# MCU021_V1_0_Target_Device.net
KiCad netlist of a schematic drawn in Altium Designer
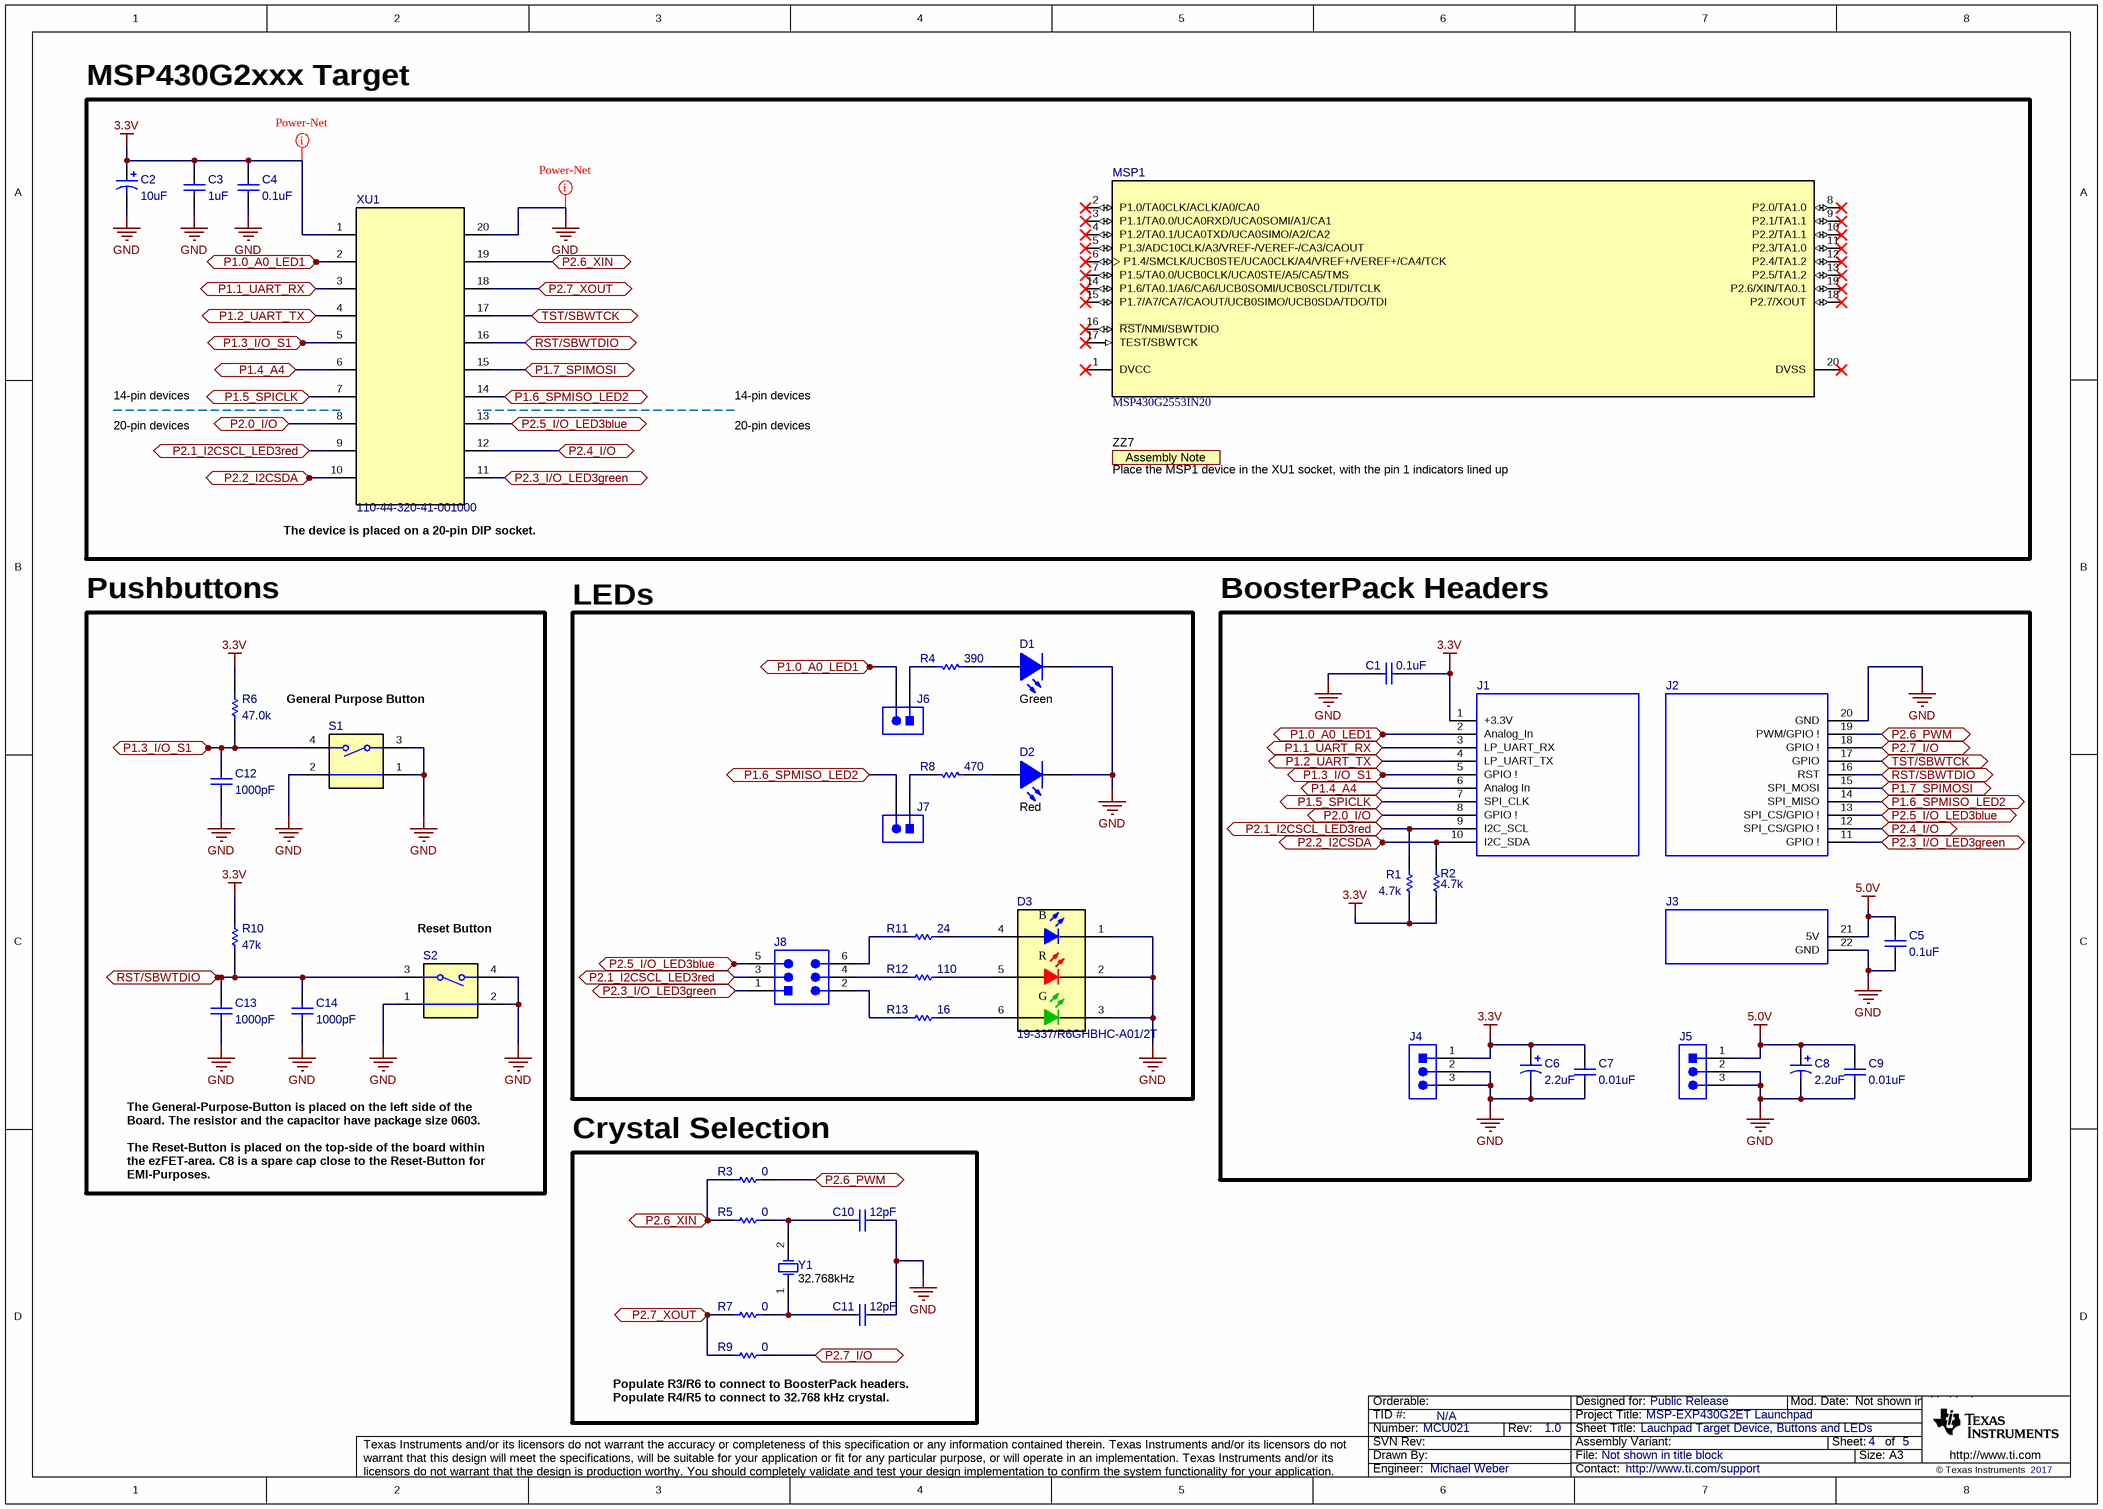
[diagram p0: MCU021_V1.0_Target_Device.SchDoc]

(export (version "E")
  (design (tool "Eeschema 10.0.6"))
  (components
    (comp (ref "C1")
      (value "0.1uF")
      (footprint "0402")
      (description "CAP, CERM, 0.1 µF, 10 V,+/- 10%, X5R, 0402")
      (fields
        (field (name "PARTNUMBER") "C1005X5R1A104K050BA")
        (field (name "MANUFACTURER") "TDK")
        (field (name "PUBLISHER") "Texas Instruments")
      )
      (libsource (lib "Capacitor_Ceramic") (part "C1005X5R1A104K050BA"))
    )
    (comp (ref "C2")
      (value "10uF")
      (footprint "3216-18")
      (description "CAP, TA, 10 µF, 10 V, +/- 20%, 3.4 ohm, SMD")
      (fields
        (field (name "PARTNUMBER") "293D106X0010A2TE3")
        (field (name "MANUFACTURER") "Vishay-Sprague")
        (field (name "PUBLISHER") "Texas Instruments")
      )
      (libsource (lib "Capacitor_Tantalum") (part "293D106X0010A2TE3"))
    )
    (comp (ref "C3")
      (value "1uF")
      (footprint "0402")
      (description "CAP, CERM, 1 µF, 10 V,+/- 10%, X5R, 0402")
      (fields
        (field (name "PARTNUMBER") "GRM155R61A105KE15D")
        (field (name "MANUFACTURER") "MuRata")
        (field (name "PUBLISHER") "Texas Instruments")
      )
      (libsource (lib "Capacitor_Ceramic") (part "GRM155R61A105KE15D"))
    )
    (comp (ref "C4")
      (value "0.1uF")
      (footprint "0402")
      (description "CAP, CERM, 0.1 µF, 10 V,+/- 10%, X5R, 0402")
      (fields
        (field (name "PARTNUMBER") "C1005X5R1A104K050BA")
        (field (name "MANUFACTURER") "TDK")
        (field (name "PUBLISHER") "Texas Instruments")
      )
      (libsource (lib "Capacitor_Ceramic") (part "C1005X5R1A104K050BA"))
    )
    (comp (ref "C5")
      (value "0.1uF")
      (footprint "0402")
      (description "CAP, CERM, 0.1 µF, 10 V,+/- 10%, X5R, 0402")
      (fields
        (field (name "PARTNUMBER") "C1005X5R1A104K050BA")
        (field (name "MANUFACTURER") "TDK")
        (field (name "PUBLISHER") "Texas Instruments")
      )
      (libsource (lib "Capacitor_Ceramic") (part "C1005X5R1A104K050BA"))
    )
    (comp (ref "C6")
      (value "2.2uF")
      (footprint "3216-18")
      (description "CAP, TA, 2.2 µF, 25 V, +/- 10%, 6.3 ohm, SMD")
      (fields
        (field (name "PARTNUMBER") "293D225X9025A2TE3")
        (field (name "MANUFACTURER") "Vishay-Sprague")
        (field (name "PUBLISHER") "Texas Instruments")
      )
      (libsource (lib "Capacitor_Tantalum") (part "293D225X9025A2TE3"))
    )
    (comp (ref "C7")
      (value "0.01uF")
      (footprint "0402")
      (description "CAP, CERM, 0.01 µF, 16 V,+/- 10%, X7R, 0402")
      (fields
        (field (name "PARTNUMBER") "GRM155R71C103KA01D")
        (field (name "MANUFACTURER") "MuRata")
        (field (name "PUBLISHER") "Texas Instruments")
      )
      (libsource (lib "Capacitor_Ceramic") (part "GRM155R71C103KA01D"))
    )
    (comp (ref "C8")
      (value "2.2uF")
      (footprint "3216-18")
      (description "CAP, TA, 2.2 µF, 25 V, +/- 10%, 6.3 ohm, SMD")
      (fields
        (field (name "PARTNUMBER") "293D225X9025A2TE3")
        (field (name "MANUFACTURER") "Vishay-Sprague")
        (field (name "PUBLISHER") "Texas Instruments")
      )
      (libsource (lib "Capacitor_Tantalum") (part "293D225X9025A2TE3"))
    )
    (comp (ref "C9")
      (value "0.01uF")
      (footprint "0402")
      (description "CAP, CERM, 0.01 µF, 16 V,+/- 10%, X7R, 0402")
      (fields
        (field (name "PARTNUMBER") "GRM155R71C103KA01D")
        (field (name "MANUFACTURER") "MuRata")
        (field (name "PUBLISHER") "Texas Instruments")
      )
      (libsource (lib "Capacitor_Ceramic") (part "GRM155R71C103KA01D"))
    )
    (comp (ref "C10")
      (value "12pF")
      (footprint "0402")
      (description "CAP, CERM, 12 pF, 50 V,+/- 5%, C0G/NP0, 0402")
      (fields
        (field (name "PARTNUMBER") "GRM1555C1H120JA01D")
        (field (name "MANUFACTURER") "MuRata")
        (field (name "PUBLISHER") "Texas Instruments")
      )
      (libsource (lib "Capacitor_Ceramic") (part "GRM1555C1H120JA01D"))
    )
    (comp (ref "C11")
      (value "12pF")
      (footprint "0402")
      (description "CAP, CERM, 12 pF, 50 V,+/- 5%, C0G/NP0, 0402")
      (fields
        (field (name "PARTNUMBER") "GRM1555C1H120JA01D")
        (field (name "MANUFACTURER") "MuRata")
        (field (name "PUBLISHER") "Texas Instruments")
      )
      (libsource (lib "Capacitor_Ceramic") (part "GRM1555C1H120JA01D"))
    )
    (comp (ref "C12")
      (value "1000pF")
      (footprint "0603")
      (description "CAP, CERM, 1000 pF, 50 V,+/- 5%, X7R, 0603")
      (fields
        (field (name "PARTNUMBER") "GRM188R71H102JA01D")
        (field (name "MANUFACTURER") "MuRata")
        (field (name "PUBLISHER") "Texas Instruments")
      )
      (libsource (lib "Capacitor_Ceramic") (part "GRM188R71H102JA01D"))
    )
    (comp (ref "C13")
      (value "1000pF")
      (footprint "0402")
      (description "CAP, CERM, 1000 pF, 50 V,+/- 10%, X7R, 0402")
      (fields
        (field (name "PARTNUMBER") "GRM155R71H102KA01D")
        (field (name "MANUFACTURER") "MuRata")
        (field (name "PUBLISHER") "Texas Instruments")
      )
      (libsource (lib "Capacitor_Ceramic") (part "GRM155R71H102KA01D"))
    )
    (comp (ref "C14")
      (value "1000pF")
      (footprint "0402")
      (description "CAP, CERM, 1000 pF, 50 V,+/- 10%, X7R, 0402")
      (fields
        (field (name "PARTNUMBER") "GRM155R71H102KA01D")
        (field (name "MANUFACTURER") "MuRata")
        (field (name "PUBLISHER") "Texas Instruments")
      )
      (libsource (lib "Capacitor_Ceramic") (part "GRM155R71H102KA01D"))
    )
    (comp (ref "D1")
      (value "Green")
      (footprint "WL-SMCW_GREEN")
      (description "LED, Green, SMD")
      (fields
        (field (name "MANUFACTURER") "Wurth Elektronik")
        (field (name "PARTNUMBER") "150060VS75000")
        (field (name "PUBLISHER") "Texas Instruments")
      )
      (libsource (lib "LED") (part "150060VS75000"))
    )
    (comp (ref "D2")
      (value "Red")
      (footprint "WL-SMCW_RED")
      (description "LED, Red, SMD")
      (fields
        (field (name "MANUFACTURER") "Wurth Elektronik")
        (field (name "PARTNUMBER") "150060RS75000")
        (field (name "PUBLISHER") "Texas Instruments")
      )
      (libsource (lib "LED") (part "150060RS75000"))
    )
    (comp (ref "D3")
      (value "19-337/R6GHBHC-A01/2T")
      (footprint "19-337_RGB")
      (description "LED, RGB, SMD")
      (fields
        (field (name "MANUFACTURER") "Everlight")
        (field (name "SYMBOLCREATOR") "Altium")
        (field (name "PUBLISHER") "Texas Instruments")
      )
      (libsource (lib "LED") (part "19-337/R6GHBHC-A01/2T"))
    )
    (comp (ref "J1")
      (value "SSQ-110-03-F-S")
      (footprint "BoosterPack_20pin_J1")
      (description "Receptacle, 2.54mm, 10x1, Gold, TH")
      (fields
        (field (name "MANUFACTURER") "Samtec")
        (field (name "ALTERNATE PARTNUMBER") "SSHQ-110-S-08-G-LF")
        (field (name "SYMBOLCREATOR") "a0412235")
        (field (name "PUBLISHER") "Texas Instruments")
      )
      (libsource (lib "Hardware") (part "BoosterPack_20pin_J1"))
    )
    (comp (ref "J2")
      (value "SSQ-110-03-F-S")
      (footprint "BoosterPack_20pin_J2")
      (description "Receptacle, 2.54mm, 10x1, Gold, TH")
      (fields
        (field (name "MANUFACTURER") "Samtec")
        (field (name "ALTERNATE PARTNUMBER") "SSHQ-110-S-08-G-LF")
        (field (name "SYMBOLCREATOR") "a0412235")
        (field (name "PUBLISHER") "Texas Instruments")
      )
      (libsource (lib "Hardware") (part "BoosterPack_20pin_J2"))
    )
    (comp (ref "J3")
      (value "SSQ-102-03-F-S")
      (footprint "BoosterPack_20pin_J3")
      (description "Receptacle, 2.54mm, 2x1, Gold, TH")
      (fields
        (field (name "MANUFACTURER") "Samtec")
        (field (name "SYMBOLCREATOR") "a0412235")
        (field (name "PUBLISHER") "Texas Instruments")
      )
      (libsource (lib "Hardware") (part "BoosterPack_20pin_J3"))
    )
    (comp (ref "J4")
      (value "PEC03SAAN")
      (footprint "PEC03SAAN_Launchpad_3V3")
      (description "Header, 100mil, 3x1, Tin, TH")
      (fields
        (field (name "MANUFACTURER") "Sullins Connector Solutions")
        (field (name "SYMBOLCREATOR") "a0412235")
        (field (name "PUBLISHER") "Texas Instruments")
      )
      (libsource (lib "Connectors_Sullins") (part "PEC03SAAN"))
    )
    (comp (ref "J5")
      (value "PEC03SAAN")
      (footprint "PEC03SAAN_Launchpad_5V0")
      (description "Header, 100mil, 3x1, Tin, TH")
      (fields
        (field (name "MANUFACTURER") "Sullins Connector Solutions")
        (field (name "SYMBOLCREATOR") "a0412235")
        (field (name "PUBLISHER") "Texas Instruments")
      )
      (libsource (lib "Connectors_Sullins") (part "PEC03SAAN"))
    )
    (comp (ref "J6")
      (value "TSW-102-07-G-S")
      (footprint "TSW-102-07-G-S")
      (description "Header, 100mil, 2x1, Gold, TH")
      (fields
        (field (name "MANUFACTURER") "Samtec")
        (field (name "SYMBOLCREATOR") "a0412235")
        (field (name "PUBLISHER") "Texas Instruments")
      )
      (libsource (lib "Connectors_Samtec") (part "TSW-102-07-G-S"))
    )
    (comp (ref "J7")
      (value "TSW-102-07-G-S")
      (footprint "TSW-102-07-G-S")
      (description "Header, 100mil, 2x1, Gold, TH")
      (fields
        (field (name "MANUFACTURER") "Samtec")
        (field (name "SYMBOLCREATOR") "a0412235")
        (field (name "PUBLISHER") "Texas Instruments")
      )
      (libsource (lib "Connectors_Samtec") (part "TSW-102-07-G-S"))
    )
    (comp (ref "J8")
      (value "TSW-103-07-G-D")
      (footprint "TSW-103-07-G-D")
      (description "Header, 100mil, 3x2, Gold, TH")
      (fields
        (field (name "MANUFACTURER") "Samtec")
        (field (name "SYMBOLCREATOR") "a0412235")
        (field (name "PUBLISHER") "Texas Instruments")
      )
      (libsource (lib "Connectors_Samtec") (part "TSW-103-07-G-D"))
    )
    (comp (ref "MSP1")
      (value "MSP430G2553IN20")
      (footprint "N0020A")
      (fields (field (name "MANUFACTURER") "Texas Instruments"))
      (libsource (lib "Altium Vault - TI") (part "CMP-0039636-1"))
    )
    (comp (ref "R1")
      (value "4.7k")
      (footprint "0402")
      (description "RES, 4.7 k, 5%, 0.063 W, 0402")
      (fields
        (field (name "PARTNUMBER") "CRCW04024K70JNED")
        (field (name "MANUFACTURER") "Vishay-Dale")
        (field (name "PUBLISHER") "Texas Instruments")
      )
      (libsource (lib "Resistor_0402") (part "CRCW04024K70JNED"))
    )
    (comp (ref "R2")
      (value "4.7k")
      (footprint "0402")
      (description "RES, 4.7 k, 5%, 0.063 W, 0402")
      (fields
        (field (name "PARTNUMBER") "CRCW04024K70JNED")
        (field (name "MANUFACTURER") "Vishay-Dale")
        (field (name "PUBLISHER") "Texas Instruments")
      )
      (libsource (lib "Resistor_0402") (part "CRCW04024K70JNED"))
    )
    (comp (ref "R3")
      (value "0")
      (footprint "0603")
      (description "RES, 0, 5%, 0.1 W, 0603")
      (fields
        (field (name "PARTNUMBER") "CRCW06030000Z0EA")
        (field (name "MANUFACTURER") "Vishay-Dale")
        (field (name "PUBLISHER") "Texas Instruments")
      )
      (libsource (lib "Resistor_0603") (part "CRCW06030000Z0EA"))
    )
    (comp (ref "R4")
      (value "390")
      (footprint "0402")
      (description "RES, 390, 5%, 0.063 W, 0402")
      (fields
        (field (name "PARTNUMBER") "CRCW0402390RJNED")
        (field (name "MANUFACTURER") "Vishay-Dale")
        (field (name "PUBLISHER") "Texas Instruments")
      )
      (libsource (lib "Resistor_0402") (part "CRCW0402390RJNED"))
    )
    (comp (ref "R5")
      (value "0")
      (footprint "0603")
      (description "RES, 0, 5%, 0.1 W, 0603")
      (fields
        (field (name "PARTNUMBER") "CRCW06030000Z0EA")
        (field (name "MANUFACTURER") "Vishay-Dale")
        (field (name "PUBLISHER") "Texas Instruments")
      )
      (libsource (lib "Resistor_0603") (part "CRCW06030000Z0EA"))
    )
    (comp (ref "R6")
      (value "47.0k")
      (footprint "0603")
      (description "RES, 47.0 k, 1%, 0.1 W, AEC-Q200 Grade 0, 0603")
      (fields
        (field (name "PARTNUMBER") "CRCW060347K0FKEA")
        (field (name "MANUFACTURER") "Vishay-Dale")
        (field (name "PUBLISHER") "Texas Instruments")
      )
      (libsource (lib "Resistor_0603") (part "CRCW060347K0FKEA"))
    )
    (comp (ref "R7")
      (value "0")
      (footprint "0603")
      (description "RES, 0, 5%, 0.1 W, 0603")
      (fields
        (field (name "PARTNUMBER") "CRCW06030000Z0EA")
        (field (name "MANUFACTURER") "Vishay-Dale")
        (field (name "PUBLISHER") "Texas Instruments")
      )
      (libsource (lib "Resistor_0603") (part "CRCW06030000Z0EA"))
    )
    (comp (ref "R8")
      (value "470")
      (footprint "0402")
      (description "RES, 470, 5%, 0.063 W, 0402")
      (fields
        (field (name "PARTNUMBER") "CRCW0402470RJNED")
        (field (name "MANUFACTURER") "Vishay-Dale")
        (field (name "PUBLISHER") "Texas Instruments")
      )
      (libsource (lib "Resistor_0402") (part "CRCW0402470RJNED"))
    )
    (comp (ref "R9")
      (value "0")
      (footprint "0603")
      (description "RES, 0, 5%, 0.1 W, 0603")
      (fields
        (field (name "PARTNUMBER") "CRCW06030000Z0EA")
        (field (name "MANUFACTURER") "Vishay-Dale")
        (field (name "PUBLISHER") "Texas Instruments")
      )
      (libsource (lib "Resistor_0603") (part "CRCW06030000Z0EA"))
    )
    (comp (ref "R10")
      (value "47k")
      (footprint "0402")
      (description "RES, 47 k, 5%, 0.063 W, 0402")
      (fields
        (field (name "PARTNUMBER") "CRCW040247K0JNED")
        (field (name "MANUFACTURER") "Vishay-Dale")
        (field (name "PUBLISHER") "Texas Instruments")
      )
      (libsource (lib "Resistor_0402") (part "CRCW040247K0JNED"))
    )
    (comp (ref "R11")
      (value "24")
      (footprint "0402")
      (description "RES, 24, 5%, 0.063 W, 0402")
      (fields
        (field (name "PARTNUMBER") "CRCW040224R0JNED")
        (field (name "MANUFACTURER") "Vishay-Dale")
        (field (name "PUBLISHER") "Texas Instruments")
      )
      (libsource (lib "Resistor_0402") (part "CRCW040224R0JNED"))
    )
    (comp (ref "R12")
      (value "110")
      (footprint "0402")
      (description "RES, 110, 1%, 0.063 W, 0402")
      (fields
        (field (name "PARTNUMBER") "CRCW0402110RFKED")
        (field (name "MANUFACTURER") "Vishay-Dale")
        (field (name "PUBLISHER") "Texas Instruments")
      )
      (libsource (lib "Resistor_0402") (part "CRCW0402110RFKED"))
    )
    (comp (ref "R13")
      (value "16")
      (footprint "0402")
      (description "RES, 16, 5%, 0.063 W, 0402")
      (fields
        (field (name "PARTNUMBER") "CRCW040216R0JNED")
        (field (name "MANUFACTURER") "Vishay-Dale")
        (field (name "PUBLISHER") "Texas Instruments")
      )
      (libsource (lib "Resistor_0402") (part "CRCW040216R0JNED"))
    )
    (comp (ref "S1")
      (value "1188E-1K2-V-TR")
      (footprint "SW_1188E")
      (description "Switch, SPST, 0.05 A, 12 VDC, SMD")
      (fields
        (field (name "MANUFACTURER") "Diptronics")
        (field (name "SYMBOLCREATOR") "Altium")
        (field (name "PUBLISHER") "Texas Instruments")
      )
      (libsource (lib "Switches") (part "1188E-1K2-V-TR"))
    )
    (comp (ref "S2")
      (value "1188E-1K2-V-TR")
      (footprint "SW_1188E")
      (description "Switch, SPST, 0.05 A, 12 VDC, SMD")
      (fields
        (field (name "MANUFACTURER") "Diptronics")
        (field (name "SYMBOLCREATOR") "Altium")
        (field (name "PUBLISHER") "Texas Instruments")
      )
      (libsource (lib "") (part "1188E-1K2-V-TR_1"))
    )
    (comp (ref "XU1")
      (value "110-44-320-41-001000")
      (footprint "Mill-Max_110-xx-320-41-001000")
      (description "Socket, DIP-20, Sleeve Pin, 2.54 mm Pitch")
      (fields
        (field (name "MANUFACTURER") "Mill-Max")
        (field (name "SYMBOLCREATOR") "a0799628")
        (field (name "PUBLISHER") "Texas Instruments")
      )
      (libsource (lib "Sockets") (part "110-44-320-41-001000"))
    )
    (comp (ref "Y1")
      (value "ECS-.327-12.5-34B-TR")
      (footprint "ECS_ECX_31B")
      (description "Crystal, 32.768 KHz, 20 ppm, SMD")
      (fields (field (name "FREQUENCY_FIXED") "32.768kHz") (field (name "MANUFACTURER") "ECS Inc."))
      (libsource (lib "Altium Vault - TI") (part "CMP-0078856-1"))
    )
    (comp (ref "ZZ7")
      (value "Place the MSP1 device in the XU1 socket, with the pin 1 indicators lined up")
      (footprint "AssemblyNote")
      (fields (field (name "SYMBOLCREATOR") "codlsc") (field (name "PUBLISHER") "Texas Instruments"))
      (libsource (lib "Hardware") (part "AssemblyNote"))
    )
  )
  (nets
    (net (code "1") (name "/P1.0_A0_LED1") (class "Default")
      (node (ref "J1") (pin "2") (pinfunction "Analog_In_2") (pintype "passive"))
      (node (ref "J6") (pin "2") (pinfunction "2_2") (pintype "passive"))
      (node (ref "XU1") (pin "2") (pinfunction "2_2") (pintype "passive"))
    )
    (net (code "2") (name "/P1.1_UART_RX") (class "Default")
      (node (ref "J1") (pin "3") (pinfunction "LP_UART_RX_3") (pintype "passive"))
      (node (ref "XU1") (pin "3") (pinfunction "3_3") (pintype "passive"))
    )
    (net (code "3") (name "/P1.2_UART_TX") (class "Default")
      (node (ref "J1") (pin "4") (pinfunction "LP_UART_TX_4") (pintype "passive"))
      (node (ref "XU1") (pin "4") (pinfunction "4_4") (pintype "passive"))
    )
    (net (code "4") (name "/P1.3_I{slash}O_S1") (class "Default")
      (node (ref "C12") (pin "1") (pinfunction "1_1") (pintype "passive"))
      (node (ref "J1") (pin "5") (pinfunction "GPIO_!_5") (pintype "passive"))
      (node (ref "R6") (pin "1") (pinfunction "1_1") (pintype "passive"))
      (node (ref "S1") (pin "4") (pinfunction "4_4") (pintype "passive"))
      (node (ref "XU1") (pin "5") (pinfunction "5_5") (pintype "passive"))
    )
    (net (code "5") (name "/P1.4_A4") (class "Default")
      (node (ref "J1") (pin "6") (pinfunction "Analog_In_6") (pintype "passive"))
      (node (ref "XU1") (pin "6") (pinfunction "6_6") (pintype "passive"))
    )
    (net (code "6") (name "/P1.5_SPICLK") (class "Default")
      (node (ref "J1") (pin "7") (pinfunction "SPI_CLK_7") (pintype "passive"))
      (node (ref "XU1") (pin "7") (pinfunction "7_7") (pintype "passive"))
    )
    (net (code "7") (name "/P1.6_SPMISO_LED2") (class "Default")
      (node (ref "J2") (pin "14") (pinfunction "SPI_MISO_14") (pintype "passive"))
      (node (ref "J7") (pin "2") (pinfunction "2_2") (pintype "passive"))
      (node (ref "XU1") (pin "14") (pinfunction "14_14") (pintype "passive"))
    )
    (net (code "8") (name "/P1.7_SPIMOSI") (class "Default")
      (node (ref "J2") (pin "15") (pinfunction "SPI_MOSI_15") (pintype "passive"))
      (node (ref "XU1") (pin "15") (pinfunction "15_15") (pintype "passive"))
    )
    (net (code "9") (name "/P2.0_I{slash}O") (class "Default")
      (node (ref "J1") (pin "8") (pinfunction "GPIO_!_8") (pintype "passive"))
      (node (ref "XU1") (pin "8") (pinfunction "8_8") (pintype "passive"))
    )
    (net (code "10") (name "/P2.1_I2CSCL_LED3red") (class "Default")
      (node (ref "J1") (pin "9") (pinfunction "I2C_SCL_9") (pintype "passive"))
      (node (ref "J8") (pin "3") (pinfunction "3_3") (pintype "passive"))
      (node (ref "R1") (pin "2") (pinfunction "2_2") (pintype "passive"))
      (node (ref "XU1") (pin "9") (pinfunction "9_9") (pintype "passive"))
    )
    (net (code "11") (name "/P2.2_I2CSDA") (class "Default")
      (node (ref "J1") (pin "10") (pinfunction "I2C_SDA_10") (pintype "passive"))
      (node (ref "R2") (pin "2") (pinfunction "2_2") (pintype "passive"))
      (node (ref "XU1") (pin "10") (pinfunction "10_10") (pintype "passive"))
    )
    (net (code "12") (name "/P2.3_I{slash}O_LED3green") (class "Default")
      (node (ref "J2") (pin "11") (pinfunction "GPIO_!_11") (pintype "passive"))
      (node (ref "J8") (pin "1") (pinfunction "1_1") (pintype "passive"))
      (node (ref "XU1") (pin "11") (pinfunction "11_11") (pintype "passive"))
    )
    (net (code "13") (name "/P2.4_I{slash}O") (class "Default")
      (node (ref "J2") (pin "12") (pinfunction "SPI_CS/GPIO_!_12") (pintype "passive"))
      (node (ref "XU1") (pin "12") (pinfunction "12_12") (pintype "passive"))
    )
    (net (code "14") (name "/P2.5_I{slash}O_LED3blue") (class "Default")
      (node (ref "J2") (pin "13") (pinfunction "SPI_CS/GPIO_!_13") (pintype "passive"))
      (node (ref "J8") (pin "5") (pinfunction "5_5") (pintype "passive"))
      (node (ref "XU1") (pin "13") (pinfunction "13_13") (pintype "passive"))
    )
    (net (code "15") (name "/P2.6_PWM") (class "Default")
      (node (ref "J2") (pin "19") (pinfunction "PWM/GPIO_!_19") (pintype "passive"))
      (node (ref "R3") (pin "2") (pinfunction "2_2") (pintype "passive"))
    )
    (net (code "16") (name "/P2.6_XIN") (class "Default")
      (node (ref "R3") (pin "1") (pinfunction "1_1") (pintype "passive"))
      (node (ref "R5") (pin "1") (pinfunction "1_1") (pintype "passive"))
      (node (ref "XU1") (pin "19") (pinfunction "19_19") (pintype "passive"))
    )
    (net (code "17") (name "/P2.7_I{slash}O") (class "Default")
      (node (ref "J2") (pin "18") (pinfunction "GPIO_!_18") (pintype "passive"))
      (node (ref "R9") (pin "2") (pinfunction "2_2") (pintype "passive"))
    )
    (net (code "18") (name "/P2.7_XOUT") (class "Default")
      (node (ref "R7") (pin "1") (pinfunction "1_1") (pintype "passive"))
      (node (ref "R9") (pin "1") (pinfunction "1_1") (pintype "passive"))
      (node (ref "XU1") (pin "18") (pinfunction "18_18") (pintype "passive"))
    )
    (net (code "19") (name "/RST{slash}SBWTDIO") (class "Default")
      (node (ref "C13") (pin "1") (pinfunction "1_1") (pintype "passive"))
      (node (ref "C14") (pin "1") (pinfunction "1_1") (pintype "passive"))
      (node (ref "J2") (pin "16") (pinfunction "RST_16") (pintype "passive"))
      (node (ref "R10") (pin "1") (pinfunction "1_1") (pintype "passive"))
      (node (ref "S2") (pin "3") (pinfunction "3_3") (pintype "passive"))
      (node (ref "XU1") (pin "16") (pinfunction "16_16") (pintype "passive"))
    )
    (net (code "20") (name "/TST{slash}SBWTCK") (class "Default")
      (node (ref "J2") (pin "17") (pinfunction "GPIO_17") (pintype "passive"))
      (node (ref "XU1") (pin "17") (pinfunction "17_17") (pintype "passive"))
    )
    (net (code "21") (name "3.3V") (class "Default")
      (node (ref "C1") (pin "1") (pinfunction "1_1") (pintype "passive"))
      (node (ref "C2") (pin "1") (pinfunction "+_1") (pintype "passive"))
      (node (ref "C3") (pin "1") (pinfunction "1_1") (pintype "passive"))
      (node (ref "C4") (pin "1") (pinfunction "1_1") (pintype "passive"))
      (node (ref "C6") (pin "1") (pinfunction "+_1") (pintype "passive"))
      (node (ref "C7") (pin "1") (pinfunction "1_1") (pintype "passive"))
      (node (ref "J1") (pin "1") (pinfunction "+3.3V_1") (pintype "power_in"))
      (node (ref "J4") (pin "1") (pinfunction "1_1") (pintype "passive"))
      (node (ref "R1") (pin "1") (pinfunction "1_1") (pintype "passive"))
      (node (ref "R10") (pin "2") (pinfunction "2_2") (pintype "passive"))
      (node (ref "R2") (pin "1") (pinfunction "1_1") (pintype "passive"))
      (node (ref "R6") (pin "2") (pinfunction "2_2") (pintype "passive"))
      (node (ref "XU1") (pin "1") (pinfunction "1_1") (pintype "passive"))
    )
    (net (code "22") (name "5.0V") (class "Default")
      (node (ref "C5") (pin "1") (pinfunction "1_1") (pintype "passive"))
      (node (ref "C8") (pin "1") (pinfunction "+_1") (pintype "passive"))
      (node (ref "C9") (pin "1") (pinfunction "1_1") (pintype "passive"))
      (node (ref "J3") (pin "21") (pinfunction "5V_21") (pintype "power_in"))
      (node (ref "J5") (pin "1") (pinfunction "1_1") (pintype "passive"))
    )
    (net (code "23") (name "GND") (class "Default")
      (node (ref "C1") (pin "2") (pinfunction "2_2") (pintype "passive"))
      (node (ref "C10") (pin "2") (pinfunction "2_2") (pintype "passive"))
      (node (ref "C11") (pin "2") (pinfunction "2_2") (pintype "passive"))
      (node (ref "C12") (pin "2") (pinfunction "2_2") (pintype "passive"))
      (node (ref "C13") (pin "2") (pinfunction "2_2") (pintype "passive"))
      (node (ref "C14") (pin "2") (pinfunction "2_2") (pintype "passive"))
      (node (ref "C2") (pin "2") (pinfunction "-_2") (pintype "passive"))
      (node (ref "C3") (pin "2") (pinfunction "2_2") (pintype "passive"))
      (node (ref "C4") (pin "2") (pinfunction "2_2") (pintype "passive"))
      (node (ref "C5") (pin "2") (pinfunction "2_2") (pintype "passive"))
      (node (ref "C6") (pin "2") (pinfunction "-_2") (pintype "passive"))
      (node (ref "C7") (pin "2") (pinfunction "2_2") (pintype "passive"))
      (node (ref "C8") (pin "2") (pinfunction "-_2") (pintype "passive"))
      (node (ref "C9") (pin "2") (pinfunction "2_2") (pintype "passive"))
      (node (ref "D1") (pin "1") (pinfunction "K_1") (pintype "passive"))
      (node (ref "D2") (pin "1") (pinfunction "K_1") (pintype "passive"))
      (node (ref "D3") (pin "1") (pinfunction "K_1") (pintype "passive"))
      (node (ref "D3") (pin "2") (pinfunction "K_2") (pintype "passive"))
      (node (ref "D3") (pin "3") (pinfunction "K_3") (pintype "passive"))
      (node (ref "J2") (pin "20") (pinfunction "GND_20") (pintype "power_in"))
      (node (ref "J3") (pin "22") (pinfunction "GND_22") (pintype "power_in"))
      (node (ref "J4") (pin "2") (pinfunction "2_2") (pintype "passive"))
      (node (ref "J4") (pin "3") (pinfunction "3_3") (pintype "passive"))
      (node (ref "J5") (pin "2") (pinfunction "2_2") (pintype "passive"))
      (node (ref "J5") (pin "3") (pinfunction "3_3") (pintype "passive"))
      (node (ref "S1") (pin "1") (pinfunction "1_1") (pintype "passive"))
      (node (ref "S1") (pin "2") (pinfunction "2_2") (pintype "passive"))
      (node (ref "S1") (pin "3") (pinfunction "3_3") (pintype "passive"))
      (node (ref "S2") (pin "1") (pinfunction "1_1") (pintype "passive"))
      (node (ref "S2") (pin "2") (pinfunction "2_2") (pintype "passive"))
      (node (ref "S2") (pin "4") (pinfunction "4_4") (pintype "passive"))
      (node (ref "XU1") (pin "20") (pinfunction "20_20") (pintype "passive"))
    )
    (net (code "24") (name "Net-(D1-A)") (class "Default")
      (node (ref "D1") (pin "2") (pinfunction "A_2") (pintype "passive"))
      (node (ref "R4") (pin "1") (pinfunction "1_1") (pintype "passive"))
    )
    (net (code "25") (name "Net-(D2-A)") (class "Default")
      (node (ref "D2") (pin "2") (pinfunction "A_2") (pintype "passive"))
      (node (ref "R8") (pin "2") (pinfunction "2_2") (pintype "passive"))
    )
    (net (code "26") (name "Net-(D3-A-Pad4)") (class "Default")
      (node (ref "D3") (pin "4") (pinfunction "A_4") (pintype "passive"))
      (node (ref "R11") (pin "2") (pinfunction "2_2") (pintype "passive"))
    )
    (net (code "27") (name "Net-(D3-A-Pad5)") (class "Default")
      (node (ref "D3") (pin "5") (pinfunction "A_5") (pintype "passive"))
      (node (ref "R12") (pin "2") (pinfunction "2_2") (pintype "passive"))
    )
    (net (code "28") (name "Net-(D3-A-Pad6)") (class "Default")
      (node (ref "D3") (pin "6") (pinfunction "A_6") (pintype "passive"))
      (node (ref "R13") (pin "2") (pinfunction "2_2") (pintype "passive"))
    )
    (net (code "29") (name "Net-(J6-Pad1)") (class "Default")
      (node (ref "J6") (pin "1") (pinfunction "1_1") (pintype "passive"))
      (node (ref "R4") (pin "2") (pinfunction "2_2") (pintype "passive"))
    )
    (net (code "30") (name "Net-(J7-Pad1)") (class "Default")
      (node (ref "J7") (pin "1") (pinfunction "1_1") (pintype "passive"))
      (node (ref "R8") (pin "1") (pinfunction "1_1") (pintype "passive"))
    )
    (net (code "31") (name "Net-(J8-Pad2)") (class "Default")
      (node (ref "J8") (pin "2") (pinfunction "2_2") (pintype "passive"))
      (node (ref "R13") (pin "1") (pinfunction "1_1") (pintype "passive"))
    )
    (net (code "32") (name "Net-(J8-Pad4)") (class "Default")
      (node (ref "J8") (pin "4") (pinfunction "4_4") (pintype "passive"))
      (node (ref "R12") (pin "1") (pinfunction "1_1") (pintype "passive"))
    )
    (net (code "33") (name "Net-(J8-Pad6)") (class "Default")
      (node (ref "J8") (pin "6") (pinfunction "6_6") (pintype "passive"))
      (node (ref "R11") (pin "1") (pinfunction "1_1") (pintype "passive"))
    )
    (net (code "34") (name "Net-(Y1-OSC1)") (class "Default")
      (node (ref "C11") (pin "1") (pinfunction "1_1") (pintype "passive"))
      (node (ref "R7") (pin "2") (pinfunction "2_2") (pintype "passive"))
      (node (ref "Y1") (pin "1") (pinfunction "OSC1_1") (pintype "passive"))
    )
    (net (code "35") (name "Net-(Y1-OSC2)") (class "Default")
      (node (ref "C10") (pin "1") (pinfunction "1_1") (pintype "passive"))
      (node (ref "R5") (pin "2") (pinfunction "2_2") (pintype "passive"))
      (node (ref "Y1") (pin "2") (pinfunction "OSC2_2") (pintype "passive"))
    )
    (net (code "36") (name "unconnected-(MSP1-DVCC-Pad1)") (class "Default")
      (node (ref "MSP1") (pin "1") (pinfunction "DVCC_1") (pintype "power_in+no_connect"))
    )
    (net (code "37") (name "unconnected-(MSP1-DVSS-Pad20)") (class "Default")
      (node (ref "MSP1") (pin "20") (pinfunction "DVSS_20") (pintype "power_in+no_connect"))
    )
    (net (code "38") (name "unconnected-(MSP1-P1.0{slash}TA0CLK{slash}ACLK{slash}A0{slash}CA0-Pad2)") (class "Default")
      (node (ref "MSP1") (pin "2") (pinfunction "P1.0/TA0CLK/ACLK/A0/CA0_2") (pintype "bidirectional+no_connect"))
    )
    (net (code "39") (name "unconnected-(MSP1-P1.1{slash}TA0.0{slash}UCA0RXD{slash}UCA0SOMI{slash}A1{slash}CA1-Pad3)") (class "Default")
      (node (ref "MSP1") (pin "3") (pinfunction "P1.1/TA0.0/UCA0RXD/UCA0SOMI/A1/CA1_3") (pintype "bidirectional+no_connect"))
    )
    (net (code "40") (name "unconnected-(MSP1-P1.2{slash}TA0.1{slash}UCA0TXD{slash}UCA0SIMO{slash}A2{slash}CA2-Pad4)") (class "Default")
      (node (ref "MSP1") (pin "4") (pinfunction "P1.2/TA0.1/UCA0TXD/UCA0SIMO/A2/CA2_4") (pintype "bidirectional+no_connect"))
    )
    (net (code "41") (name "unconnected-(MSP1-P1.3{slash}ADC10CLK{slash}A3{slash}VREF-{slash}VEREF-{slash}CA3{slash}CAOUT-Pad5)") (class "Default")
      (node (ref "MSP1") (pin "5") (pinfunction "P1.3/ADC10CLK/A3/VREF-/VEREF-/CA3/CAOUT_5") (pintype "bidirectional+no_connect"))
    )
    (net (code "42") (name "unconnected-(MSP1-P1.4{slash}SMCLK{slash}UCB0STE{slash}UCA0CLK{slash}A4{slash}VREF+{slash}VEREF+{slash}CA4{slash}TCK-Pad6)") (class "Default")
      (node (ref "MSP1") (pin "6") (pinfunction "P1.4/SMCLK/UCB0STE/UCA0CLK/A4/VREF+/VEREF+/CA4/TCK_6") (pintype "bidirectional+no_connect"))
    )
    (net (code "43") (name "unconnected-(MSP1-P1.5{slash}TA0.0{slash}UCB0CLK{slash}UCA0STE{slash}A5{slash}CA5{slash}TMS-Pad7)") (class "Default")
      (node (ref "MSP1") (pin "7") (pinfunction "P1.5/TA0.0/UCB0CLK/UCA0STE/A5/CA5/TMS_7") (pintype "bidirectional+no_connect"))
    )
    (net (code "44") (name "unconnected-(MSP1-P1.6{slash}TA0.1{slash}A6{slash}CA6{slash}UCB0SOMI{slash}UCB0SCL{slash}TDI{slash}TCLK-Pad14)") (class "Default")
      (node (ref "MSP1") (pin "14") (pinfunction "P1.6/TA0.1/A6/CA6/UCB0SOMI/UCB0SCL/TDI/TCLK_14") (pintype "bidirectional+no_connect"))
    )
    (net (code "45") (name "unconnected-(MSP1-P1.7{slash}A7{slash}CA7{slash}CAOUT{slash}UCB0SIMO{slash}UCB0SDA{slash}TDO{slash}TDI-Pad15)") (class "Default")
      (node (ref "MSP1") (pin "15") (pinfunction "P1.7/A7/CA7/CAOUT/UCB0SIMO/UCB0SDA/TDO/TDI_15") (pintype "bidirectional+no_connect"))
    )
    (net (code "46") (name "unconnected-(MSP1-P2.0{slash}TA1.0-Pad8)") (class "Default")
      (node (ref "MSP1") (pin "8") (pinfunction "P2.0/TA1.0_8") (pintype "bidirectional+no_connect"))
    )
    (net (code "47") (name "unconnected-(MSP1-P2.1{slash}TA1.1-Pad9)") (class "Default")
      (node (ref "MSP1") (pin "9") (pinfunction "P2.1/TA1.1_9") (pintype "bidirectional+no_connect"))
    )
    (net (code "48") (name "unconnected-(MSP1-P2.2{slash}TA1.1-Pad10)") (class "Default")
      (node (ref "MSP1") (pin "10") (pinfunction "P2.2/TA1.1_10") (pintype "bidirectional+no_connect"))
    )
    (net (code "49") (name "unconnected-(MSP1-P2.3{slash}TA1.0-Pad11)") (class "Default")
      (node (ref "MSP1") (pin "11") (pinfunction "P2.3/TA1.0_11") (pintype "bidirectional+no_connect"))
    )
    (net (code "50") (name "unconnected-(MSP1-P2.4{slash}TA1.2-Pad12)") (class "Default")
      (node (ref "MSP1") (pin "12") (pinfunction "P2.4/TA1.2_12") (pintype "bidirectional+no_connect"))
    )
    (net (code "51") (name "unconnected-(MSP1-P2.5{slash}TA1.2-Pad13)") (class "Default")
      (node (ref "MSP1") (pin "13") (pinfunction "P2.5/TA1.2_13") (pintype "bidirectional+no_connect"))
    )
    (net (code "52") (name "unconnected-(MSP1-P2.6{slash}XIN{slash}TA0.1-Pad19)") (class "Default")
      (node (ref "MSP1") (pin "19") (pinfunction "P2.6/XIN/TA0.1_19") (pintype "bidirectional+no_connect"))
    )
    (net (code "53") (name "unconnected-(MSP1-P2.7{slash}XOUT-Pad18)") (class "Default")
      (node (ref "MSP1") (pin "18") (pinfunction "P2.7/XOUT_18") (pintype "bidirectional+no_connect"))
    )
    (net (code "54") (name "unconnected-(MSP1-TEST{slash}SBWTCK-Pad17)") (class "Default")
      (node (ref "MSP1") (pin "17") (pinfunction "TEST/SBWTCK_17") (pintype "input+no_connect"))
    )
    (net (code "55") (name "unconnected-(MSP1-~{RST}{slash}NMI{slash}SBWTDIO-Pad16)") (class "Default")
      (node (ref "MSP1") (pin "16") (pinfunction "~{RST}/NMI/SBWTDIO_16") (pintype "bidirectional+no_connect"))
    )
  )
)
